# BSS138LevelShift.net
KiCad netlist of a schematic drawn in EAGLE
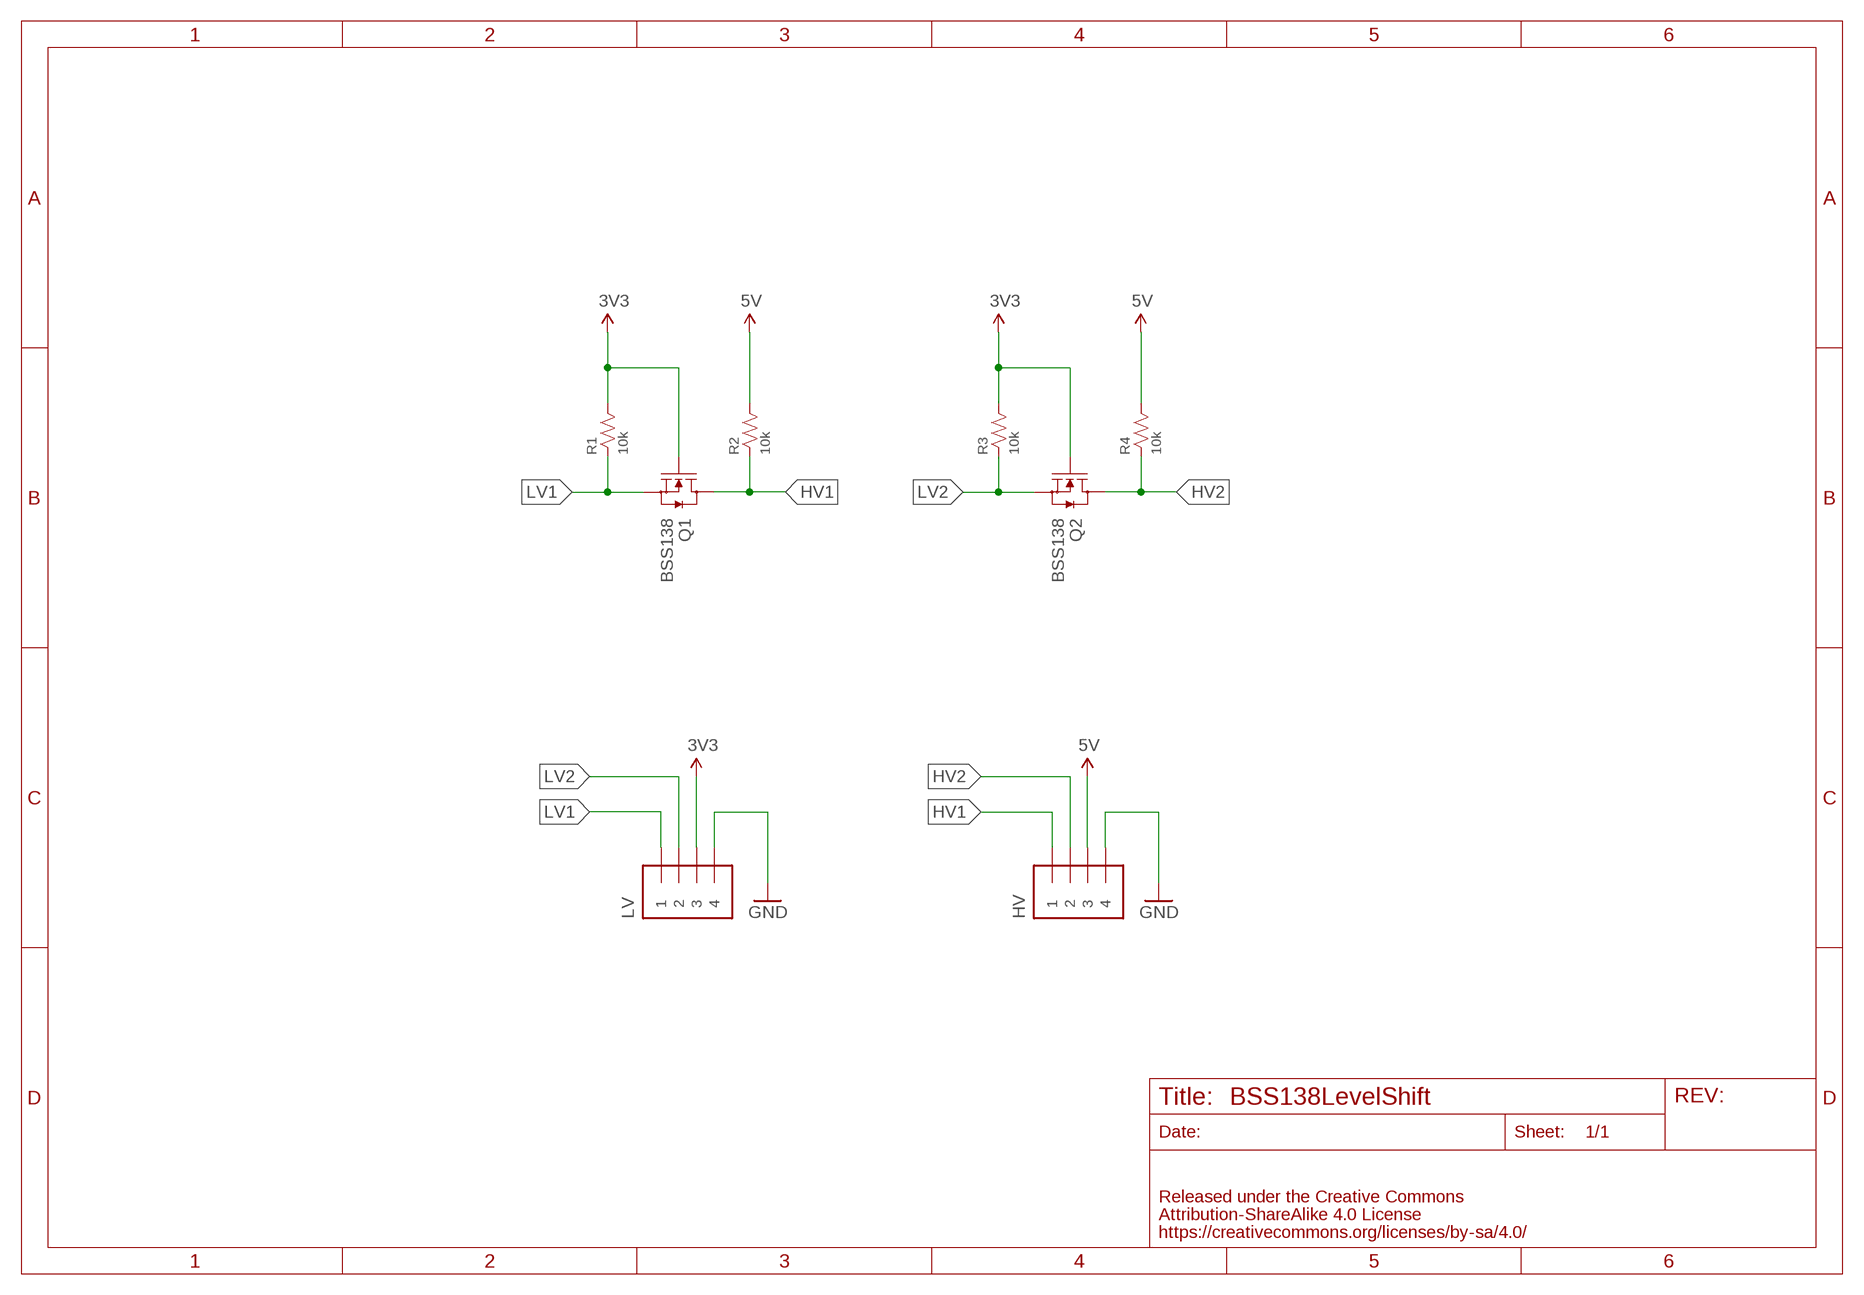
[diagram p0: schematic, sheet 1]

(export (version "E")
  (design (tool "Eeschema 10.0.6"))
  (components
    (comp (ref "HV")
      (value "PIN_HEADER_1X4")
      (footprint "eagle-import:PIN_1X4_SNEAKY")
      (libsource (lib "eagle-import") (part "PIN_HEADER_1X4"))
    )
    (comp (ref "LV")
      (value "PIN_HEADER_1X4")
      (footprint "eagle-import:PIN_1X4_SNEAKY")
      (libsource (lib "eagle-import") (part "PIN_HEADER_1X4"))
    )
    (comp (ref "Q1")
      (value "BSS138")
      (footprint "eagle-import:SOT23-3")
      (libsource (lib "eagle-import") (part "MOSFET-N-BSS138"))
    )
    (comp (ref "Q2")
      (value "BSS138")
      (footprint "eagle-import:SOT23-3")
      (libsource (lib "eagle-import") (part "MOSFET-N-BSS138"))
    )
    (comp (ref "R1")
      (value "10k")
      (footprint "eagle-import:0603")
      (libsource (lib "eagle-import") (part "RESISTOR-0603"))
    )
    (comp (ref "R2")
      (value "10k")
      (footprint "eagle-import:0603")
      (libsource (lib "eagle-import") (part "RESISTOR-0603"))
    )
    (comp (ref "R3")
      (value "10k")
      (footprint "eagle-import:0603")
      (libsource (lib "eagle-import") (part "RESISTOR-0603"))
    )
    (comp (ref "R4")
      (value "10k")
      (footprint "eagle-import:0603")
      (libsource (lib "eagle-import") (part "RESISTOR-0603"))
    )
  )
  (nets
    (net (code "1") (name "3V3") (class "Default")
      (node (ref "LV") (pin "3") (pinfunction "3_3") (pintype "bidirectional"))
      (node (ref "Q1") (pin "1") (pinfunction "G_1") (pintype "passive"))
      (node (ref "Q2") (pin "1") (pinfunction "G_1") (pintype "passive"))
      (node (ref "R1") (pin "2") (pinfunction "2_2") (pintype "bidirectional"))
      (node (ref "R3") (pin "2") (pinfunction "2_2") (pintype "bidirectional"))
    )
    (net (code "2") (name "5V") (class "Default")
      (node (ref "HV") (pin "3") (pinfunction "3_3") (pintype "bidirectional"))
      (node (ref "R2") (pin "2") (pinfunction "2_2") (pintype "bidirectional"))
      (node (ref "R4") (pin "2") (pinfunction "2_2") (pintype "bidirectional"))
    )
    (net (code "3") (name "GND") (class "Default")
      (node (ref "HV") (pin "4") (pinfunction "4_4") (pintype "bidirectional"))
      (node (ref "LV") (pin "4") (pinfunction "4_4") (pintype "bidirectional"))
    )
    (net (code "4") (name "HV1") (class "Default")
      (node (ref "HV") (pin "1") (pinfunction "1_1") (pintype "bidirectional"))
      (node (ref "Q1") (pin "3") (pinfunction "D_3") (pintype "passive"))
      (node (ref "R2") (pin "1") (pinfunction "1_1") (pintype "bidirectional"))
    )
    (net (code "5") (name "HV2") (class "Default")
      (node (ref "HV") (pin "2") (pinfunction "2_2") (pintype "bidirectional"))
      (node (ref "Q2") (pin "3") (pinfunction "D_3") (pintype "passive"))
      (node (ref "R4") (pin "1") (pinfunction "1_1") (pintype "bidirectional"))
    )
    (net (code "6") (name "LV1") (class "Default")
      (node (ref "LV") (pin "1") (pinfunction "1_1") (pintype "bidirectional"))
      (node (ref "Q1") (pin "2") (pinfunction "S_2") (pintype "passive"))
      (node (ref "R1") (pin "1") (pinfunction "1_1") (pintype "bidirectional"))
    )
    (net (code "7") (name "LV2") (class "Default")
      (node (ref "LV") (pin "2") (pinfunction "2_2") (pintype "bidirectional"))
      (node (ref "Q2") (pin "2") (pinfunction "S_2") (pintype "passive"))
      (node (ref "R3") (pin "1") (pinfunction "1_1") (pintype "bidirectional"))
    )
  )
)
